# sparkfun-battery-babysitter.net
KiCad netlist of a schematic drawn in EAGLE
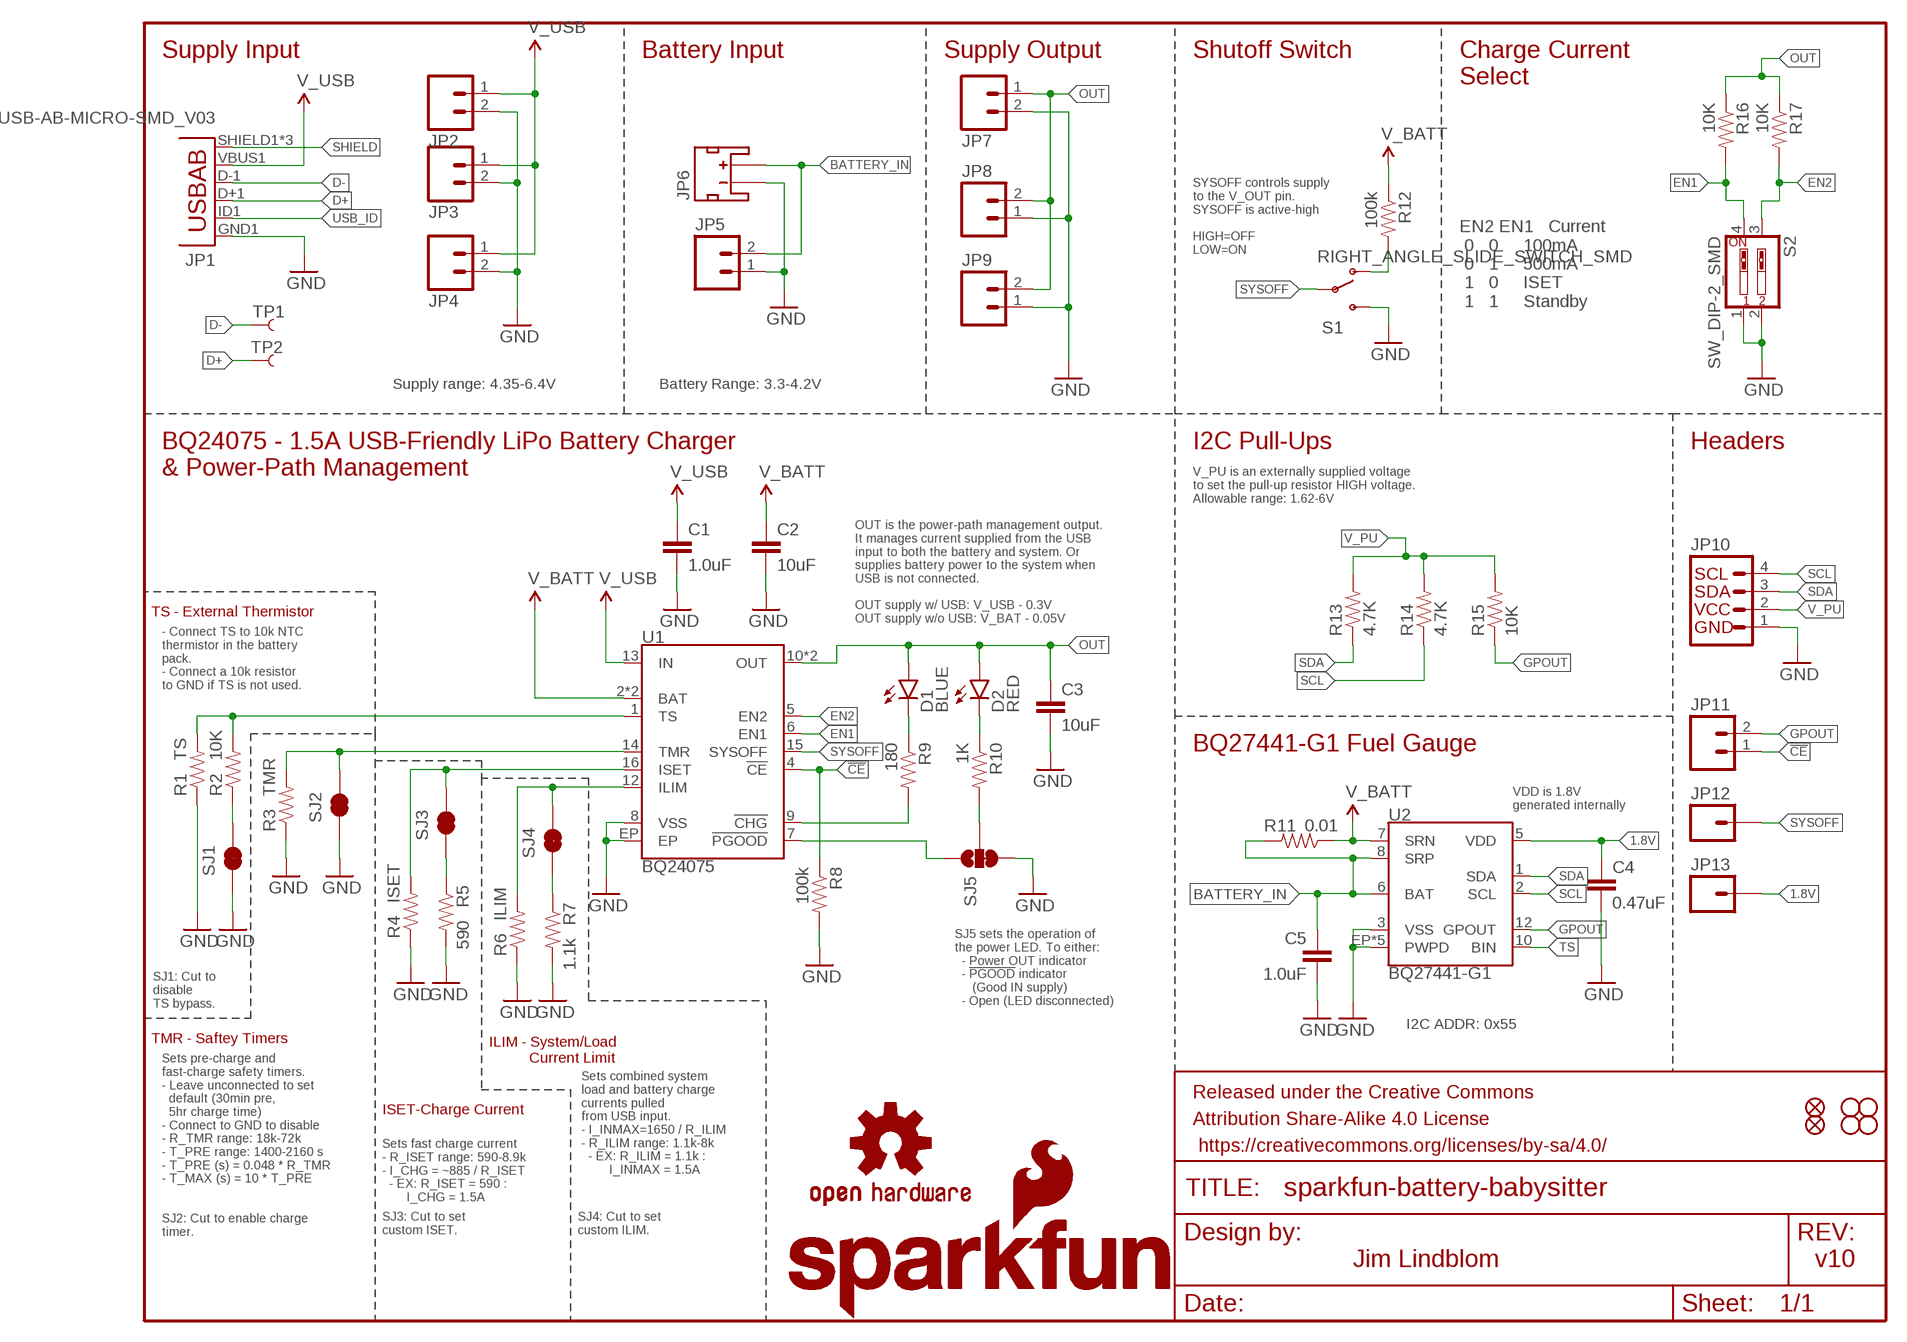
[diagram p0: schematic, sheet 1]

(export (version "E")
  (design (tool "Eeschema 10.0.6"))
  (components
    (comp (ref "C1")
      (value "1.0uF")
      (footprint "eagle-import:1206-CAP")
      (libsource (lib "eagle-import") (part "1.0UF50V10%(1206)"))
    )
    (comp (ref "C2")
      (value "10uF")
      (footprint "eagle-import:0805-CAP")
      (libsource (lib "eagle-import") (part "10UF10V10%(0805)"))
    )
    (comp (ref "C3")
      (value "10uF")
      (footprint "eagle-import:0805-CAP")
      (libsource (lib "eagle-import") (part "10UF10V10%(0805)"))
    )
    (comp (ref "C4")
      (value "0.47uF")
      (footprint "eagle-import:0603-CAP")
      (libsource (lib "eagle-import") (part "CAP0603-CAP"))
    )
    (comp (ref "C5")
      (value "1.0uF")
      (footprint "eagle-import:0603-CAP")
      (libsource (lib "eagle-import") (part "1.0UF-16V-10%(0603)"))
    )
    (comp (ref "D1")
      (value "BLUE")
      (footprint "eagle-import:LED-0603")
      (libsource (lib "eagle-import") (part "LED-BLUE0603"))
    )
    (comp (ref "D2")
      (value "RED")
      (footprint "eagle-import:LED-0603")
      (libsource (lib "eagle-import") (part "LED-RED0603"))
    )
    (comp (ref "FID1")
      (value "FIDUCIAL1X2")
      (footprint "eagle-import:FIDUCIAL-1X2")
      (libsource (lib "eagle-import") (part "FIDUCIAL1X2"))
    )
    (comp (ref "FID2")
      (value "FIDUCIAL1X2")
      (footprint "eagle-import:FIDUCIAL-1X2")
      (libsource (lib "eagle-import") (part "FIDUCIAL1X2"))
    )
    (comp (ref "FRAME1")
      (value "FRAME-LETTER")
      (footprint "eagle-import:CREATIVE_COMMONS")
      (libsource (lib "eagle-import") (part "FRAME-LETTER"))
    )
    (comp (ref "JP1")
      (value "USB-AB-MICRO-SMD_V03")
      (footprint "eagle-import:USB-AB-MICRO-SMD_V03")
      (libsource (lib "eagle-import") (part "USB-ABCONN-11794"))
    )
    (comp (ref "JP2")
      (value "M021X02_NO_SILK")
      (footprint "eagle-import:1X02_NO_SILK")
      (libsource (lib "eagle-import") (part "M021X02_NO_SILK"))
    )
    (comp (ref "JP3")
      (value "M023.5MM-NO_SILK")
      (footprint "eagle-import:SCREWTERMINAL-3.5MM-2-NS")
      (libsource (lib "eagle-import") (part "M023.5MM-NO_SILK"))
    )
    (comp (ref "JP4")
      (value "M021X02_NO_SILK")
      (footprint "eagle-import:1X02_NO_SILK")
      (libsource (lib "eagle-import") (part "M021X02_NO_SILK"))
    )
    (comp (ref "JP5")
      (value "M021X02_NO_SILK")
      (footprint "eagle-import:1X02_NO_SILK")
      (libsource (lib "eagle-import") (part "M021X02_NO_SILK"))
    )
    (comp (ref "JP6")
      (value "JST_2MM_MALE")
      (footprint "eagle-import:JST-2-SMD")
      (libsource (lib "eagle-import") (part "JST_2MM_MALE"))
    )
    (comp (ref "JP7")
      (value "M023.5MM-NO_SILK")
      (footprint "eagle-import:SCREWTERMINAL-3.5MM-2-NS")
      (libsource (lib "eagle-import") (part "M023.5MM-NO_SILK"))
    )
    (comp (ref "JP8")
      (value "M021X02_NO_SILK")
      (footprint "eagle-import:1X02_NO_SILK")
      (libsource (lib "eagle-import") (part "M021X02_NO_SILK"))
    )
    (comp (ref "JP9")
      (value "M02-JST-2-PTH-NO_SILK")
      (footprint "eagle-import:JST-2-PTH-NS")
      (libsource (lib "eagle-import") (part "M02-JST-2-PTH-NO_SILK"))
    )
    (comp (ref "JP10")
      (value "I2C_STANDARD_NO_SILK")
      (footprint "eagle-import:1X04_NO_SILK")
      (libsource (lib "eagle-import") (part "I2C_STANDARD_NO_SILK"))
    )
    (comp (ref "JP11")
      (value "M021X02_NO_SILK")
      (footprint "eagle-import:1X02_NO_SILK")
      (libsource (lib "eagle-import") (part "M021X02_NO_SILK"))
    )
    (comp (ref "JP12")
      (value "M01PTH_NO_SILK_YES_STOP")
      (footprint "eagle-import:1X01_NO_SILK")
      (libsource (lib "eagle-import") (part "M01PTH_NO_SILK_YES_STOP"))
    )
    (comp (ref "JP13")
      (value "M01PTH_NO_SILK_YES_STOP")
      (footprint "eagle-import:1X01_NO_SILK")
      (libsource (lib "eagle-import") (part "M01PTH_NO_SILK_YES_STOP"))
    )
    (comp (ref "LOGO1")
      (value "SFE_LOGO_NAME.1_INCH")
      (footprint "eagle-import:SFE_LOGO_NAME_.1")
      (libsource (lib "eagle-import") (part "SFE_LOGO_NAME.1_INCH"))
    )
    (comp (ref "LOGO2")
      (value "SFE_LOGO_NAME_FLAME.1_INCH")
      (footprint "eagle-import:SFE_LOGO_NAME_FLAME_.1")
      (libsource (lib "eagle-import") (part "SFE_LOGO_NAME_FLAME.1_INCH"))
    )
    (comp (ref "LOGO3")
      (value "OSHW-LOGOS")
      (footprint "eagle-import:OSHW-LOGO-S")
      (libsource (lib "eagle-import") (part "OSHW-LOGOS"))
    )
    (comp (ref "R1")
      (value "TS")
      (footprint "eagle-import:1_6W-RES")
      (libsource (lib "eagle-import") (part "SparkFun-Resistors_RESISTORPTH-1/6W"))
    )
    (comp (ref "R2")
      (value "10K")
      (footprint "eagle-import:0603-RES")
      (libsource (lib "eagle-import") (part "10KOHM-1/10W-1%(0603)0603"))
    )
    (comp (ref "R3")
      (value "TMR")
      (footprint "eagle-import:1_6W-RES")
      (libsource (lib "eagle-import") (part "SparkFun-Resistors_RESISTORPTH-1/6W"))
    )
    (comp (ref "R4")
      (value "ISET")
      (footprint "eagle-import:1_6W-RES")
      (libsource (lib "eagle-import") (part "SparkFun-Resistors_RESISTORPTH-1/6W"))
    )
    (comp (ref "R5")
      (value "590")
      (footprint "eagle-import:0603-RES")
      (libsource (lib "eagle-import") (part "RESISTOR0603-RES"))
    )
    (comp (ref "R6")
      (value "ILIM")
      (footprint "eagle-import:1_6W-RES")
      (libsource (lib "eagle-import") (part "SparkFun-Resistors_RESISTORPTH-1/6W"))
    )
    (comp (ref "R7")
      (value "1.1k")
      (footprint "eagle-import:0603-RES")
      (libsource (lib "eagle-import") (part "RESISTOR0603-RES"))
    )
    (comp (ref "R8")
      (value "100k")
      (footprint "eagle-import:0603-RES")
      (libsource (lib "eagle-import") (part "100KOHM-1/10W-1%(0603)"))
    )
    (comp (ref "R9")
      (value "180")
      (footprint "eagle-import:0603-RES")
      (libsource (lib "eagle-import") (part "180OHM1/10W1%(0603)"))
    )
    (comp (ref "R10")
      (value "1K")
      (footprint "eagle-import:0603-RES")
      (libsource (lib "eagle-import") (part "1KOHM-1/10W-1%(0603)"))
    )
    (comp (ref "R11")
      (value "0.01")
      (footprint "eagle-import:1206")
      (libsource (lib "eagle-import") (part "SparkFun-Resistors_RESISTOR1206"))
    )
    (comp (ref "R12")
      (value "100k")
      (footprint "eagle-import:0603-RES")
      (libsource (lib "eagle-import") (part "100KOHM-1/10W-1%(0603)"))
    )
    (comp (ref "R13")
      (value "4.7K")
      (footprint "eagle-import:0603-RES")
      (libsource (lib "eagle-import") (part "4.7KOHM-1/10W-1%(0603)"))
    )
    (comp (ref "R14")
      (value "4.7K")
      (footprint "eagle-import:0603-RES")
      (libsource (lib "eagle-import") (part "4.7KOHM-1/10W-1%(0603)"))
    )
    (comp (ref "R15")
      (value "10K")
      (footprint "eagle-import:0603-RES")
      (libsource (lib "eagle-import") (part "10KOHM-1/10W-1%(0603)0603"))
    )
    (comp (ref "R16")
      (value "10K")
      (footprint "eagle-import:0603-RES")
      (libsource (lib "eagle-import") (part "10KOHM-1/10W-1%(0603)0603"))
    )
    (comp (ref "R17")
      (value "10K")
      (footprint "eagle-import:0603-RES")
      (libsource (lib "eagle-import") (part "10KOHM-1/10W-1%(0603)0603"))
    )
    (comp (ref "S1")
      (value "RIGHT_ANGLE_SLIDE_SWITCH_SMD")
      (footprint "eagle-import:SWITCH-SPST-SMD-A")
      (libsource (lib "eagle-import") (part "SWITCH-SPDT-SMD-A"))
    )
    (comp (ref "S2")
      (value "SW_DIP-2_SMD")
      (footprint "eagle-import:DIPSWITCH-02-50MIL")
      (libsource (lib "eagle-import") (part "SW_DIP-2-SMT-HALFSIZE"))
    )
    (comp (ref "SJ1")
      (value "JUMPER-PAD-2-NC_BY_TRACE")
      (footprint "eagle-import:PAD-JUMPER-2-NC_BY_TRACE_YES_SILK")
      (libsource (lib "eagle-import") (part "JUMPER-PAD-2-NC_BY_TRACE"))
    )
    (comp (ref "SJ2")
      (value "JUMPER-PAD-2-NC_BY_TRACE")
      (footprint "eagle-import:PAD-JUMPER-2-NC_BY_TRACE_YES_SILK")
      (libsource (lib "eagle-import") (part "JUMPER-PAD-2-NC_BY_TRACE"))
    )
    (comp (ref "SJ3")
      (value "JUMPER-PAD-2-NC_BY_TRACE")
      (footprint "eagle-import:PAD-JUMPER-2-NC_BY_TRACE_YES_SILK")
      (libsource (lib "eagle-import") (part "JUMPER-PAD-2-NC_BY_TRACE"))
    )
    (comp (ref "SJ4")
      (value "JUMPER-PAD-2-NC_BY_TRACE")
      (footprint "eagle-import:PAD-JUMPER-2-NC_BY_TRACE_YES_SILK")
      (libsource (lib "eagle-import") (part "JUMPER-PAD-2-NC_BY_TRACE"))
    )
    (comp (ref "SJ5")
      (value "JUMPER-PAD-3-2OF3_NC_BY_TRACE_SMALL")
      (footprint "eagle-import:PAD-JUMPER-3-2OF3_NC_BY_TRACE_YES_SILK_FULL_BOX")
      (libsource (lib "eagle-import") (part "JUMPER-PAD-3-2OF3_NC_BY_TRACE_SMALL"))
    )
    (comp (ref "STANDOFF1")
      (value "STAND-OFF")
      (footprint "eagle-import:STAND-OFF")
      (libsource (lib "eagle-import") (part "STAND-OFF"))
    )
    (comp (ref "STANDOFF2")
      (value "STAND-OFF")
      (footprint "eagle-import:STAND-OFF")
      (libsource (lib "eagle-import") (part "STAND-OFF"))
    )
    (comp (ref "STANDOFF3")
      (value "STAND-OFF")
      (footprint "eagle-import:STAND-OFF")
      (libsource (lib "eagle-import") (part "STAND-OFF"))
    )
    (comp (ref "STANDOFF4")
      (value "STAND-OFF")
      (footprint "eagle-import:STAND-OFF")
      (libsource (lib "eagle-import") (part "STAND-OFF"))
    )
    (comp (ref "TP1")
      (value "TEST-POINT3X4")
      (footprint "eagle-import:PAD.03X.04")
      (libsource (lib "eagle-import") (part "TEST-POINT3X4"))
    )
    (comp (ref "TP2")
      (value "TEST-POINT3X4")
      (footprint "eagle-import:PAD.03X.04")
      (libsource (lib "eagle-import") (part "TEST-POINT3X4"))
    )
    (comp (ref "U1")
      (value "BQ24075")
      (footprint "eagle-import:PVQFN-N16")
      (fields (field (name "PROD_ID") "IC-13219"))
      (libsource (lib "eagle-import") (part "BQ24075"))
    )
    (comp (ref "U2")
      (value "BQ27441-G1")
      (footprint "eagle-import:PDSO-N12")
      (fields (field (name "PROD_ID") "IC-13220"))
      (libsource (lib "eagle-import") (part "BQ27441-G1"))
    )
  )
  (nets
    (net (code "1") (name "/~{CE}") (class "Default")
      (node (ref "JP11") (pin "1") (pinfunction "1_1") (pintype "passive"))
      (node (ref "R8") (pin "1") (pinfunction "1_1") (pintype "passive"))
      (node (ref "U1") (pin "4") (pinfunction "~{CE}_4") (pintype "bidirectional"))
    )
    (net (code "2") (name "1.8V") (class "Default")
      (node (ref "C4") (pin "1") (pinfunction "1_1") (pintype "passive"))
      (node (ref "JP13") (pin "1") (pinfunction "1_1") (pintype "passive"))
      (node (ref "U2") (pin "5") (pinfunction "VDD_5") (pintype "bidirectional"))
    )
    (net (code "3") (name "BATTERY_IN") (class "Default")
      (node (ref "C5") (pin "1") (pinfunction "1_1") (pintype "passive"))
      (node (ref "JP5") (pin "2") (pinfunction "2_2") (pintype "passive"))
      (node (ref "JP6") (pin "2") (pinfunction "+_2") (pintype "bidirectional"))
      (node (ref "R11") (pin "2") (pinfunction "2_2") (pintype "passive"))
      (node (ref "U2") (pin "6") (pinfunction "BAT_6") (pintype "bidirectional"))
      (node (ref "U2") (pin "8") (pinfunction "SRP_8") (pintype "bidirectional"))
    )
    (net (code "4") (name "D+") (class "Default")
      (node (ref "JP1") (pin "D+1") (pinfunction "D+_D+1") (pintype "bidirectional"))
      (node (ref "TP2") (pin "P$1") (pinfunction "1_P$1") (pintype "bidirectional"))
    )
    (net (code "5") (name "D-") (class "Default")
      (node (ref "JP1") (pin "D-1") (pinfunction "D-_D-1") (pintype "bidirectional"))
      (node (ref "TP1") (pin "P$1") (pinfunction "1_P$1") (pintype "bidirectional"))
    )
    (net (code "6") (name "EN1") (class "Default")
      (node (ref "R16") (pin "2") (pinfunction "2_2") (pintype "passive"))
      (node (ref "S2") (pin "4") (pinfunction "4_4") (pintype "passive"))
      (node (ref "U1") (pin "6") (pinfunction "EN1_6") (pintype "bidirectional"))
    )
    (net (code "7") (name "EN2") (class "Default")
      (node (ref "R17") (pin "2") (pinfunction "2_2") (pintype "passive"))
      (node (ref "S2") (pin "3") (pinfunction "3_3") (pintype "passive"))
      (node (ref "U1") (pin "5") (pinfunction "EN2_5") (pintype "bidirectional"))
    )
    (net (code "8") (name "GND") (class "Default")
      (node (ref "C1") (pin "2") (pinfunction "2_2") (pintype "passive"))
      (node (ref "C2") (pin "2") (pinfunction "2_2") (pintype "passive"))
      (node (ref "C3") (pin "2") (pinfunction "2_2") (pintype "passive"))
      (node (ref "C4") (pin "2") (pinfunction "2_2") (pintype "passive"))
      (node (ref "C5") (pin "2") (pinfunction "2_2") (pintype "passive"))
      (node (ref "JP1") (pin "GND1") (pinfunction "GND_GND1") (pintype "bidirectional"))
      (node (ref "JP10") (pin "1") (pinfunction "1_1") (pintype "passive"))
      (node (ref "JP2") (pin "2") (pinfunction "2_2") (pintype "passive"))
      (node (ref "JP3") (pin "2") (pinfunction "2_2") (pintype "passive"))
      (node (ref "JP4") (pin "2") (pinfunction "2_2") (pintype "passive"))
      (node (ref "JP5") (pin "1") (pinfunction "1_1") (pintype "passive"))
      (node (ref "JP6") (pin "1") (pinfunction "-_1") (pintype "bidirectional"))
      (node (ref "JP7") (pin "2") (pinfunction "2_2") (pintype "passive"))
      (node (ref "JP8") (pin "1") (pinfunction "1_1") (pintype "passive"))
      (node (ref "JP9") (pin "1") (pinfunction "1_1") (pintype "passive"))
      (node (ref "R1") (pin "1") (pinfunction "1_1") (pintype "passive"))
      (node (ref "R3") (pin "1") (pinfunction "1_1") (pintype "passive"))
      (node (ref "R4") (pin "1") (pinfunction "1_1") (pintype "passive"))
      (node (ref "R5") (pin "2") (pinfunction "2_2") (pintype "passive"))
      (node (ref "R6") (pin "1") (pinfunction "1_1") (pintype "passive"))
      (node (ref "R7") (pin "2") (pinfunction "2_2") (pintype "passive"))
      (node (ref "R8") (pin "2") (pinfunction "2_2") (pintype "passive"))
      (node (ref "S1") (pin "3") (pinfunction "S_3") (pintype "passive"))
      (node (ref "S2") (pin "1") (pinfunction "1_1") (pintype "passive"))
      (node (ref "S2") (pin "2") (pinfunction "2_2") (pintype "passive"))
      (node (ref "SJ1") (pin "1") (pinfunction "1_1") (pintype "passive"))
      (node (ref "SJ2") (pin "1") (pinfunction "1_1") (pintype "passive"))
      (node (ref "SJ5") (pin "3") (pinfunction "3_3") (pintype "passive"))
      (node (ref "U1") (pin "8") (pinfunction "VSS_8") (pintype "bidirectional"))
      (node (ref "U1") (pin "EP") (pinfunction "EP_EP") (pintype "bidirectional"))
      (node (ref "U2") (pin "3") (pinfunction "VSS_3") (pintype "bidirectional"))
      (node (ref "U2") (pin "EP") (pinfunction "PWPD_EP") (pintype "bidirectional"))
      (node (ref "U2") (pin "EP1") (pinfunction "PWPD_EP1") (pintype "bidirectional"))
      (node (ref "U2") (pin "EP2") (pinfunction "PWPD_EP2") (pintype "bidirectional"))
      (node (ref "U2") (pin "EP3") (pinfunction "PWPD_EP3") (pintype "bidirectional"))
      (node (ref "U2") (pin "EP4") (pinfunction "PWPD_EP4") (pintype "bidirectional"))
    )
    (net (code "9") (name "GPOUT") (class "Default")
      (node (ref "JP11") (pin "2") (pinfunction "2_2") (pintype "passive"))
      (node (ref "R15") (pin "1") (pinfunction "1_1") (pintype "passive"))
      (node (ref "U2") (pin "12") (pinfunction "GPOUT_12") (pintype "bidirectional"))
    )
    (net (code "10") (name "Net-(D1-PadC)") (class "Default")
      (node (ref "D1") (pin "C") (pinfunction "C_C") (pintype "passive"))
      (node (ref "R9") (pin "1") (pinfunction "1_1") (pintype "passive"))
    )
    (net (code "11") (name "Net-(D2-PadC)") (class "Default")
      (node (ref "D2") (pin "C") (pinfunction "C_C") (pintype "passive"))
      (node (ref "R10") (pin "1") (pinfunction "1_1") (pintype "passive"))
    )
    (net (code "12") (name "Net-(R2-Pad1)") (class "Default")
      (node (ref "R2") (pin "1") (pinfunction "1_1") (pintype "passive"))
      (node (ref "SJ1") (pin "2") (pinfunction "2_2") (pintype "passive"))
    )
    (net (code "13") (name "Net-(R5-Pad1)") (class "Default")
      (node (ref "R5") (pin "1") (pinfunction "1_1") (pintype "passive"))
      (node (ref "SJ3") (pin "1") (pinfunction "1_1") (pintype "passive"))
    )
    (net (code "14") (name "Net-(R7-Pad1)") (class "Default")
      (node (ref "R7") (pin "1") (pinfunction "1_1") (pintype "passive"))
      (node (ref "SJ4") (pin "1") (pinfunction "1_1") (pintype "passive"))
    )
    (net (code "15") (name "Net-(R10-Pad2)") (class "Default")
      (node (ref "R10") (pin "2") (pinfunction "2_2") (pintype "passive"))
      (node (ref "SJ5") (pin "2") (pinfunction "2_2") (pintype "passive"))
    )
    (net (code "16") (name "Net-(S1-O)") (class "Default")
      (node (ref "R12") (pin "2") (pinfunction "2_2") (pintype "passive"))
      (node (ref "S1") (pin "1") (pinfunction "O_1") (pintype "passive"))
    )
    (net (code "17") (name "Net-(U1-ILIM)") (class "Default")
      (node (ref "R6") (pin "2") (pinfunction "2_2") (pintype "passive"))
      (node (ref "SJ4") (pin "2") (pinfunction "2_2") (pintype "passive"))
      (node (ref "U1") (pin "12") (pinfunction "ILIM_12") (pintype "bidirectional"))
    )
    (net (code "18") (name "Net-(U1-ISET)") (class "Default")
      (node (ref "R4") (pin "2") (pinfunction "2_2") (pintype "passive"))
      (node (ref "SJ3") (pin "2") (pinfunction "2_2") (pintype "passive"))
      (node (ref "U1") (pin "16") (pinfunction "ISET_16") (pintype "bidirectional"))
    )
    (net (code "19") (name "Net-(U1-TMR)") (class "Default")
      (node (ref "R3") (pin "2") (pinfunction "2_2") (pintype "passive"))
      (node (ref "SJ2") (pin "2") (pinfunction "2_2") (pintype "passive"))
      (node (ref "U1") (pin "14") (pinfunction "TMR_14") (pintype "bidirectional"))
    )
    (net (code "20") (name "Net-(U1-~{CHG})") (class "Default")
      (node (ref "R9") (pin "2") (pinfunction "2_2") (pintype "passive"))
      (node (ref "U1") (pin "9") (pinfunction "~{CHG}_9") (pintype "bidirectional"))
    )
    (net (code "21") (name "Net-(U1-~{PGOOD})") (class "Default")
      (node (ref "SJ5") (pin "1") (pinfunction "1_1") (pintype "passive"))
      (node (ref "U1") (pin "7") (pinfunction "~{PGOOD}_7") (pintype "bidirectional"))
    )
    (net (code "22") (name "OUT") (class "Default")
      (node (ref "C3") (pin "1") (pinfunction "1_1") (pintype "passive"))
      (node (ref "D1") (pin "A") (pinfunction "A_A") (pintype "passive"))
      (node (ref "D2") (pin "A") (pinfunction "A_A") (pintype "passive"))
      (node (ref "JP7") (pin "1") (pinfunction "1_1") (pintype "passive"))
      (node (ref "JP8") (pin "2") (pinfunction "2_2") (pintype "passive"))
      (node (ref "JP9") (pin "2") (pinfunction "2_2") (pintype "passive"))
      (node (ref "R16") (pin "1") (pinfunction "1_1") (pintype "passive"))
      (node (ref "R17") (pin "1") (pinfunction "1_1") (pintype "passive"))
      (node (ref "U1") (pin "10") (pinfunction "OUT_10") (pintype "bidirectional"))
      (node (ref "U1") (pin "11") (pinfunction "OUT_11") (pintype "bidirectional"))
    )
    (net (code "23") (name "SCL") (class "Default")
      (node (ref "JP10") (pin "4") (pinfunction "4_4") (pintype "passive"))
      (node (ref "R14") (pin "1") (pinfunction "1_1") (pintype "passive"))
      (node (ref "U2") (pin "2") (pinfunction "SCL_2") (pintype "bidirectional"))
    )
    (net (code "24") (name "SDA") (class "Default")
      (node (ref "JP10") (pin "3") (pinfunction "3_3") (pintype "passive"))
      (node (ref "R13") (pin "1") (pinfunction "1_1") (pintype "passive"))
      (node (ref "U2") (pin "1") (pinfunction "SDA_1") (pintype "bidirectional"))
    )
    (net (code "25") (name "SHIELD") (class "Default")
      (node (ref "JP1") (pin "SHIELD1") (pinfunction "SHIELD_SHIELD1") (pintype "bidirectional"))
      (node (ref "JP1") (pin "SHIELD2") (pinfunction "SHIELD_SHIELD2") (pintype "bidirectional"))
      (node (ref "JP1") (pin "SHIELD3") (pinfunction "SHIELD_SHIELD3") (pintype "bidirectional"))
    )
    (net (code "26") (name "SYSOFF") (class "Default")
      (node (ref "JP12") (pin "1") (pinfunction "1_1") (pintype "passive"))
      (node (ref "S1") (pin "2") (pinfunction "P_2") (pintype "passive"))
      (node (ref "U1") (pin "15") (pinfunction "SYSOFF_15") (pintype "bidirectional"))
    )
    (net (code "27") (name "TS") (class "Default")
      (node (ref "R1") (pin "2") (pinfunction "2_2") (pintype "passive"))
      (node (ref "R2") (pin "2") (pinfunction "2_2") (pintype "passive"))
      (node (ref "U1") (pin "1") (pinfunction "TS_1") (pintype "bidirectional"))
      (node (ref "U2") (pin "10") (pinfunction "BIN_10") (pintype "bidirectional"))
    )
    (net (code "28") (name "USB_ID") (class "Default")
      (node (ref "JP1") (pin "ID1") (pinfunction "USBID_ID1") (pintype "bidirectional"))
    )
    (net (code "29") (name "V_BATT") (class "Default")
      (node (ref "C2") (pin "1") (pinfunction "1_1") (pintype "passive"))
      (node (ref "R11") (pin "1") (pinfunction "1_1") (pintype "passive"))
      (node (ref "R12") (pin "1") (pinfunction "1_1") (pintype "passive"))
      (node (ref "U1") (pin "2") (pinfunction "BAT_2") (pintype "bidirectional"))
      (node (ref "U1") (pin "3") (pinfunction "BAT_3") (pintype "bidirectional"))
      (node (ref "U2") (pin "7") (pinfunction "SRN_7") (pintype "bidirectional"))
    )
    (net (code "30") (name "V_PU") (class "Default")
      (node (ref "JP10") (pin "2") (pinfunction "2_2") (pintype "passive"))
      (node (ref "R13") (pin "2") (pinfunction "2_2") (pintype "passive"))
      (node (ref "R14") (pin "2") (pinfunction "2_2") (pintype "passive"))
      (node (ref "R15") (pin "2") (pinfunction "2_2") (pintype "passive"))
    )
    (net (code "31") (name "V_USB") (class "Default")
      (node (ref "C1") (pin "1") (pinfunction "1_1") (pintype "passive"))
      (node (ref "JP1") (pin "VBUS1") (pinfunction "VBUS_VBUS1") (pintype "bidirectional"))
      (node (ref "JP2") (pin "1") (pinfunction "1_1") (pintype "passive"))
      (node (ref "JP3") (pin "1") (pinfunction "1_1") (pintype "passive"))
      (node (ref "JP4") (pin "1") (pinfunction "1_1") (pintype "passive"))
      (node (ref "U1") (pin "13") (pinfunction "IN_13") (pintype "bidirectional"))
    )
    (net (code "32") (name "unconnected-(JP6-PAD1-PadNC1)") (class "Default")
      (node (ref "JP6") (pin "NC1") (pinfunction "PAD1_NC1") (pintype "bidirectional"))
    )
    (net (code "33") (name "unconnected-(JP6-PAD2-PadNC2)") (class "Default")
      (node (ref "JP6") (pin "NC2") (pinfunction "PAD2_NC2") (pintype "bidirectional"))
    )
  )
)
